# DRO.net
KiCad netlist of a schematic drawn in EAGLE
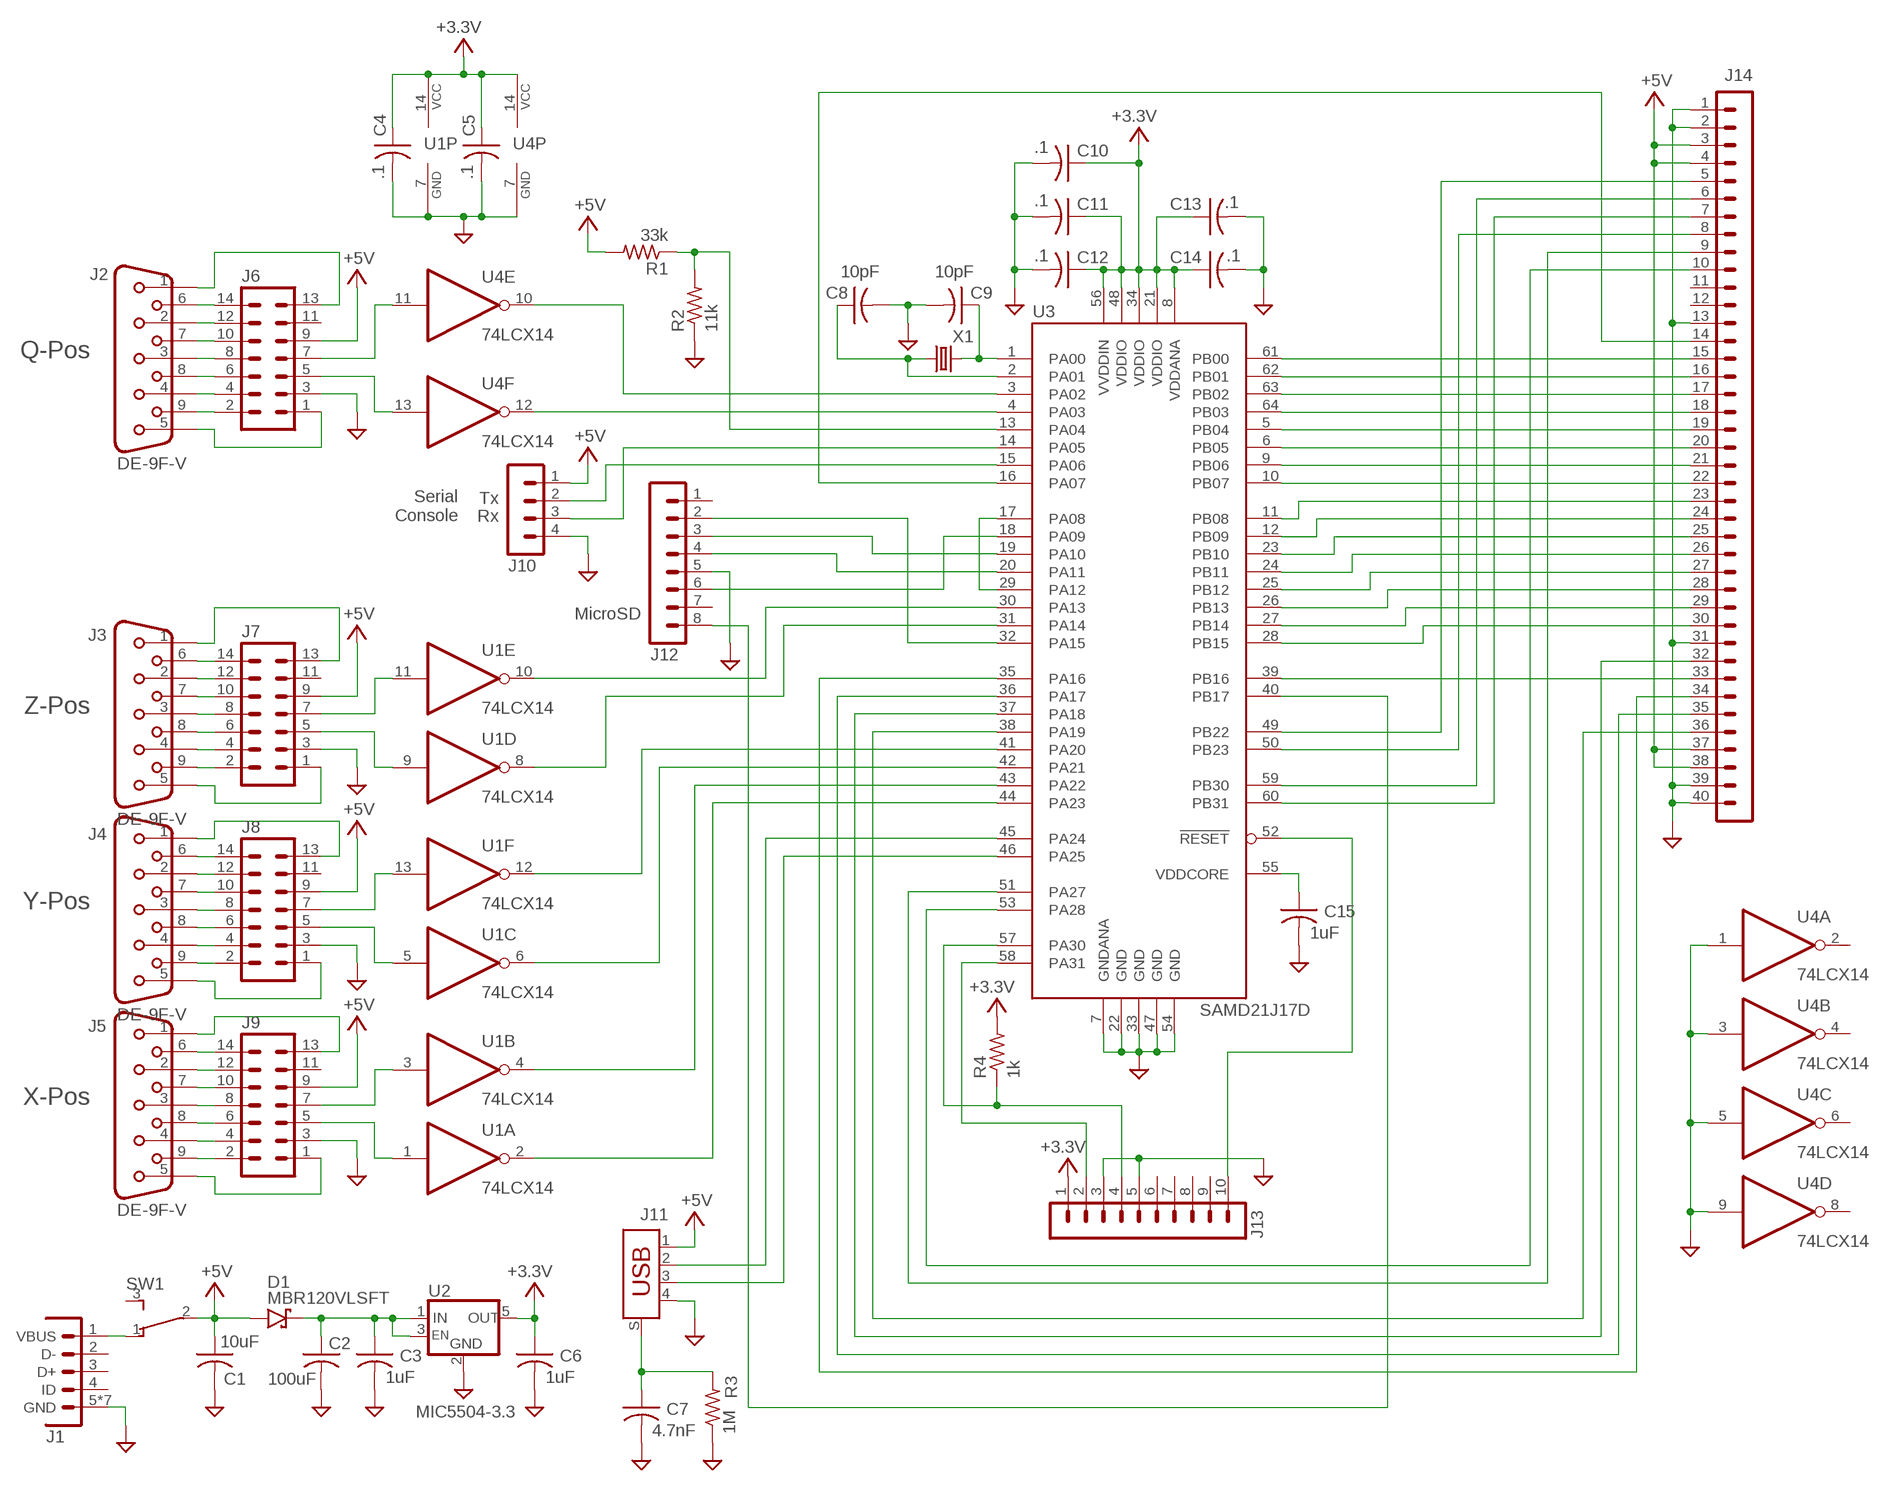
[diagram p0: schematic, sheet 1]

(export (version "E")
  (design (tool "Eeschema 10.0.6"))
  (components
    (comp (ref "C1")
      (value "10uF")
      (footprint "eagle-import:0603")
      (libsource (lib "eagle-import") (part "C-US0603"))
    )
    (comp (ref "C2")
      (value "100uF")
      (footprint "eagle-import:C1206")
      (libsource (lib "eagle-import") (part "C-USC1206"))
    )
    (comp (ref "C3")
      (value "1uF")
      (footprint "eagle-import:0603")
      (libsource (lib "eagle-import") (part "C-US0603"))
    )
    (comp (ref "C4")
      (value ".1")
      (footprint "eagle-import:0603")
      (libsource (lib "eagle-import") (part "C-US0603"))
    )
    (comp (ref "C5")
      (value ".1")
      (footprint "eagle-import:0603")
      (libsource (lib "eagle-import") (part "C-US0603"))
    )
    (comp (ref "C6")
      (value "1uF")
      (footprint "eagle-import:0603")
      (libsource (lib "eagle-import") (part "C-US0603"))
    )
    (comp (ref "C7")
      (value "4.7nF")
      (footprint "eagle-import:0603")
      (libsource (lib "eagle-import") (part "C-US0603"))
    )
    (comp (ref "C8")
      (value "10pF")
      (footprint "eagle-import:0603")
      (libsource (lib "eagle-import") (part "C-US0603"))
    )
    (comp (ref "C9")
      (value "10pF")
      (footprint "eagle-import:0603")
      (libsource (lib "eagle-import") (part "C-US0603"))
    )
    (comp (ref "C10")
      (value ".1")
      (footprint "eagle-import:0603")
      (libsource (lib "eagle-import") (part "C-US0603"))
    )
    (comp (ref "C11")
      (value ".1")
      (footprint "eagle-import:0603")
      (libsource (lib "eagle-import") (part "C-US0603"))
    )
    (comp (ref "C12")
      (value ".1")
      (footprint "eagle-import:0603")
      (libsource (lib "eagle-import") (part "C-US0603"))
    )
    (comp (ref "C13")
      (value ".1")
      (footprint "eagle-import:0603")
      (libsource (lib "eagle-import") (part "C-US0603"))
    )
    (comp (ref "C14")
      (value ".1")
      (footprint "eagle-import:0603")
      (libsource (lib "eagle-import") (part "C-US0603"))
    )
    (comp (ref "C15")
      (value "1uF")
      (footprint "eagle-import:0603")
      (libsource (lib "eagle-import") (part "C-US0603"))
    )
    (comp (ref "D1")
      (value "MBR120VLSFT")
      (footprint "eagle-import:SOD123")
      (libsource (lib "eagle-import") (part "SCHOTTKY-DIODE-SOD-123"))
    )
    (comp (ref "J1")
      (value "USB_MINI-B-MICRO-B_FCI")
      (footprint "eagle-import:USB_MICRO-B_FCI")
      (libsource (lib "eagle-import") (part "USB_MINI-B-MICRO-B_FCI"))
    )
    (comp (ref "J2")
      (value "DE-9F-V")
      (footprint "eagle-import:DE-9F-PCB-VERT")
      (libsource (lib "eagle-import") (part "DE-9F-V"))
    )
    (comp (ref "J3")
      (value "DE-9F-V")
      (footprint "eagle-import:DE-9F-PCB-VERT")
      (libsource (lib "eagle-import") (part "DE-9F-V"))
    )
    (comp (ref "J4")
      (value "DE-9F-V")
      (footprint "eagle-import:DE-9F-PCB-VERT")
      (libsource (lib "eagle-import") (part "DE-9F-V"))
    )
    (comp (ref "J5")
      (value "DE-9F-V")
      (footprint "eagle-import:DE-9F-PCB-VERT")
      (libsource (lib "eagle-import") (part "DE-9F-V"))
    )
    (comp (ref "J6")
      (value "CONN-14-BIDI")
      (footprint "eagle-import:CONN-1.27X2-14")
      (libsource (lib "eagle-import") (part "CONN-14-BIDI"))
    )
    (comp (ref "J7")
      (value "CONN-14-BIDI")
      (footprint "eagle-import:CONN-1.27X2-14")
      (libsource (lib "eagle-import") (part "CONN-14-BIDI"))
    )
    (comp (ref "J8")
      (value "CONN-14-BIDI")
      (footprint "eagle-import:CONN-1.27X2-14")
      (libsource (lib "eagle-import") (part "CONN-14-BIDI"))
    )
    (comp (ref "J9")
      (value "CONN-14-BIDI")
      (footprint "eagle-import:CONN-1.27X2-14")
      (libsource (lib "eagle-import") (part "CONN-14-BIDI"))
    )
    (comp (ref "J10")
      (value "CONN-4-2.54X1-RA")
      (footprint "eagle-import:CONN-2.54X1-4-RA")
      (libsource (lib "eagle-import") (part "CONN-4-2.54X1-RA"))
    )
    (comp (ref "J11")
      (value "USB-A-SHIELD")
      (footprint "eagle-import:USB-A")
      (libsource (lib "eagle-import") (part "USB-A-SHIELD"))
    )
    (comp (ref "J12")
      (value "CONN-8-2.54X2")
      (footprint "eagle-import:CONN-2.54X2-8")
      (libsource (lib "eagle-import") (part "CONN-8-2.54X2"))
    )
    (comp (ref "J13")
      (value "CONN-10-ARM")
      (footprint "eagle-import:CONN-1.27X2-10")
      (libsource (lib "eagle-import") (part "CONN-10-ARM"))
    )
    (comp (ref "J14")
      (value "CONN-40")
      (footprint "eagle-import:CONN-2.54X2-40")
      (libsource (lib "eagle-import") (part "CONN-40"))
    )
    (comp (ref "R1")
      (value "33k")
      (footprint "eagle-import:0603")
      (libsource (lib "eagle-import") (part "R-US0603"))
    )
    (comp (ref "R2")
      (value "11k")
      (footprint "eagle-import:0603")
      (libsource (lib "eagle-import") (part "R-US0603"))
    )
    (comp (ref "R3")
      (value "1M")
      (footprint "eagle-import:0603")
      (libsource (lib "eagle-import") (part "R-US0603"))
    )
    (comp (ref "R4")
      (value "1k")
      (footprint "eagle-import:0603")
      (libsource (lib "eagle-import") (part "R-US0603"))
    )
    (comp (ref "SW1")
      (value "SWITCH-SPDT-MINI-RA-SHORT")
      (footprint "eagle-import:SWITCH-SPDT-MINI-RA-SHORT")
      (libsource (lib "eagle-import") (part "SWITCH-SPDT-MINI-RA-SHORT"))
    )
    (comp (ref "U1")
      (value "74LCX14")
      (footprint "eagle-import:TSSOP14")
      (libsource (lib "eagle-import") (part "7404M"))
    )
    (comp (ref "U2")
      (value "MIC5504-3.3")
      (footprint "eagle-import:SOT23-5")
      (libsource (lib "eagle-import") (part "VREG-ENABLE"))
    )
    (comp (ref "U3")
      (value "SAMD21J17D")
      (footprint "eagle-import:TQFP64-0.5")
      (libsource (lib "eagle-import") (part "ATSAMD21JA"))
    )
    (comp (ref "U4")
      (value "74LCX14")
      (footprint "eagle-import:TSSOP14")
      (libsource (lib "eagle-import") (part "7404M"))
    )
    (comp (ref "X1")
      (value "CRYSTAL-3X1.5")
      (footprint "eagle-import:XTAL-SMD-3.2X1.5-2PIN")
      (libsource (lib "eagle-import") (part "CRYSTAL-3X1.5"))
    )
  )
  (nets
    (net (code "1") (name "+3.3V") (class "Default")
      (node (ref "C10") (pin "1") (pinfunction "1_1") (pintype "passive"))
      (node (ref "C11") (pin "1") (pinfunction "1_1") (pintype "passive"))
      (node (ref "C12") (pin "1") (pinfunction "1_1") (pintype "passive"))
      (node (ref "C13") (pin "1") (pinfunction "1_1") (pintype "passive"))
      (node (ref "C14") (pin "1") (pinfunction "1_1") (pintype "passive"))
      (node (ref "C4") (pin "1") (pinfunction "1_1") (pintype "passive"))
      (node (ref "C5") (pin "1") (pinfunction "1_1") (pintype "passive"))
      (node (ref "C6") (pin "1") (pinfunction "1_1") (pintype "passive"))
      (node (ref "J13") (pin "1") (pinfunction "1_1") (pintype "passive"))
      (node (ref "R4") (pin "2") (pinfunction "2_2") (pintype "passive"))
      (node (ref "U1") (pin "14") (pinfunction "VCC_14") (pintype "power_in"))
      (node (ref "U2") (pin "5") (pinfunction "OUT_5") (pintype "passive"))
      (node (ref "U3") (pin "21") (pinfunction "VDDIO_21") (pintype "power_in"))
      (node (ref "U3") (pin "34") (pinfunction "VDDIO_34") (pintype "power_in"))
      (node (ref "U3") (pin "48") (pinfunction "VDDIO_48") (pintype "power_in"))
      (node (ref "U3") (pin "56") (pinfunction "VVDDIN_56") (pintype "power_in"))
      (node (ref "U3") (pin "8") (pinfunction "VDDANA_8") (pintype "power_in"))
      (node (ref "U4") (pin "14") (pinfunction "VCC_14") (pintype "power_in"))
    )
    (net (code "2") (name "+5V") (class "Default")
      (node (ref "C1") (pin "1") (pinfunction "1_1") (pintype "passive"))
      (node (ref "D1") (pin "A") (pinfunction "A_A") (pintype "passive"))
      (node (ref "J10") (pin "1") (pinfunction "1_1") (pintype "passive"))
      (node (ref "J11") (pin "1") (pinfunction "1_1") (pintype "passive"))
      (node (ref "J14") (pin "3") (pinfunction "P3_3") (pintype "passive"))
      (node (ref "J14") (pin "37") (pinfunction "P37_37") (pintype "passive"))
      (node (ref "J14") (pin "38") (pinfunction "P38_38") (pintype "passive"))
      (node (ref "J14") (pin "4") (pinfunction "P4_4") (pintype "passive"))
      (node (ref "J6") (pin "9") (pinfunction "9_9") (pintype "passive"))
      (node (ref "J7") (pin "9") (pinfunction "9_9") (pintype "passive"))
      (node (ref "J8") (pin "9") (pinfunction "9_9") (pintype "passive"))
      (node (ref "J9") (pin "9") (pinfunction "9_9") (pintype "passive"))
      (node (ref "R1") (pin "2") (pinfunction "2_2") (pintype "passive"))
      (node (ref "SW1") (pin "2") (pinfunction "C_2") (pintype "passive"))
    )
    (net (code "3") (name "GND") (class "Default")
      (node (ref "C1") (pin "2") (pinfunction "2_2") (pintype "passive"))
      (node (ref "C10") (pin "2") (pinfunction "2_2") (pintype "passive"))
      (node (ref "C11") (pin "2") (pinfunction "2_2") (pintype "passive"))
      (node (ref "C12") (pin "2") (pinfunction "2_2") (pintype "passive"))
      (node (ref "C13") (pin "2") (pinfunction "2_2") (pintype "passive"))
      (node (ref "C14") (pin "2") (pinfunction "2_2") (pintype "passive"))
      (node (ref "C15") (pin "2") (pinfunction "2_2") (pintype "passive"))
      (node (ref "C2") (pin "2") (pinfunction "2_2") (pintype "passive"))
      (node (ref "C3") (pin "2") (pinfunction "2_2") (pintype "passive"))
      (node (ref "C4") (pin "2") (pinfunction "2_2") (pintype "passive"))
      (node (ref "C5") (pin "2") (pinfunction "2_2") (pintype "passive"))
      (node (ref "C6") (pin "2") (pinfunction "2_2") (pintype "passive"))
      (node (ref "C7") (pin "2") (pinfunction "2_2") (pintype "passive"))
      (node (ref "C8") (pin "2") (pinfunction "2_2") (pintype "passive"))
      (node (ref "C9") (pin "2") (pinfunction "2_2") (pintype "passive"))
      (node (ref "J1") (pin "5") (pinfunction "GND_5") (pintype "power_in"))
      (node (ref "J1") (pin "SHELL1") (pinfunction "GND_SHELL1") (pintype "power_in"))
      (node (ref "J1") (pin "SHELL2") (pinfunction "GND_SHELL2") (pintype "power_in"))
      (node (ref "J1") (pin "SHELL3") (pinfunction "GND_SHELL3") (pintype "power_in"))
      (node (ref "J1") (pin "SHELL4") (pinfunction "GND_SHELL4") (pintype "power_in"))
      (node (ref "J1") (pin "SHELL5") (pinfunction "GND_SHELL5") (pintype "power_in"))
      (node (ref "J1") (pin "SHELL6") (pinfunction "GND_SHELL6") (pintype "power_in"))
      (node (ref "J10") (pin "4") (pinfunction "4_4") (pintype "passive"))
      (node (ref "J11") (pin "4") (pinfunction "4_4") (pintype "passive"))
      (node (ref "J12") (pin "5") (pinfunction "5_5") (pintype "passive"))
      (node (ref "J13") (pin "3") (pinfunction "3_3") (pintype "passive"))
      (node (ref "J13") (pin "5") (pinfunction "5_5") (pintype "passive"))
      (node (ref "J14") (pin "1") (pinfunction "P1_1") (pintype "passive"))
      (node (ref "J14") (pin "13") (pinfunction "P13_13") (pintype "passive"))
      (node (ref "J14") (pin "2") (pinfunction "P2_2") (pintype "passive"))
      (node (ref "J14") (pin "31") (pinfunction "P31_31") (pintype "passive"))
      (node (ref "J14") (pin "39") (pinfunction "P39_39") (pintype "passive"))
      (node (ref "J14") (pin "40") (pinfunction "P40_40") (pintype "passive"))
      (node (ref "J6") (pin "3") (pinfunction "3_3") (pintype "passive"))
      (node (ref "J7") (pin "3") (pinfunction "3_3") (pintype "passive"))
      (node (ref "J8") (pin "3") (pinfunction "3_3") (pintype "passive"))
      (node (ref "J9") (pin "3") (pinfunction "3_3") (pintype "passive"))
      (node (ref "R2") (pin "1") (pinfunction "1_1") (pintype "passive"))
      (node (ref "R3") (pin "1") (pinfunction "1_1") (pintype "passive"))
      (node (ref "U1") (pin "7") (pinfunction "GND_7") (pintype "power_in"))
      (node (ref "U2") (pin "2") (pinfunction "GND_2") (pintype "power_in"))
      (node (ref "U3") (pin "22") (pinfunction "GND_22") (pintype "power_in"))
      (node (ref "U3") (pin "33") (pinfunction "GND_33") (pintype "power_in"))
      (node (ref "U3") (pin "47") (pinfunction "GND_47") (pintype "power_in"))
      (node (ref "U3") (pin "54") (pinfunction "GND_54") (pintype "power_in"))
      (node (ref "U3") (pin "7") (pinfunction "GNDANA_7") (pintype "power_in"))
      (node (ref "U4") (pin "1") (pinfunction "I_1") (pintype "input"))
      (node (ref "U4") (pin "3") (pinfunction "I_3") (pintype "input"))
      (node (ref "U4") (pin "5") (pinfunction "I_5") (pintype "input"))
      (node (ref "U4") (pin "7") (pinfunction "GND_7") (pintype "power_in"))
      (node (ref "U4") (pin "9") (pinfunction "I_9") (pintype "input"))
    )
    (net (code "4") (name "Net-(J1-VBUS)") (class "Default")
      (node (ref "J1") (pin "1") (pinfunction "VBUS_1") (pintype "power_in"))
      (node (ref "SW1") (pin "1") (pinfunction "NC_1") (pintype "passive"))
    )
    (net (code "5") (name "Net-(J2-Pad1)") (class "Default")
      (node (ref "J2") (pin "1") (pinfunction "1_1") (pintype "passive"))
      (node (ref "J6") (pin "13") (pinfunction "13_13") (pintype "passive"))
    )
    (net (code "6") (name "Net-(J2-Pad2)") (class "Default")
      (node (ref "J2") (pin "2") (pinfunction "2_2") (pintype "passive"))
      (node (ref "J6") (pin "12") (pinfunction "12_12") (pintype "passive"))
    )
    (net (code "7") (name "Net-(J2-Pad3)") (class "Default")
      (node (ref "J2") (pin "3") (pinfunction "3_3") (pintype "passive"))
      (node (ref "J6") (pin "8") (pinfunction "8_8") (pintype "passive"))
    )
    (net (code "8") (name "Net-(J2-Pad4)") (class "Default")
      (node (ref "J2") (pin "4") (pinfunction "4_4") (pintype "passive"))
      (node (ref "J6") (pin "4") (pinfunction "4_4") (pintype "passive"))
    )
    (net (code "9") (name "Net-(J2-Pad5)") (class "Default")
      (node (ref "J2") (pin "5") (pinfunction "5_5") (pintype "passive"))
      (node (ref "J6") (pin "1") (pinfunction "1_1") (pintype "passive"))
    )
    (net (code "10") (name "Net-(J2-Pad6)") (class "Default")
      (node (ref "J2") (pin "6") (pinfunction "6_6") (pintype "passive"))
      (node (ref "J6") (pin "14") (pinfunction "14_14") (pintype "passive"))
    )
    (net (code "11") (name "Net-(J2-Pad7)") (class "Default")
      (node (ref "J2") (pin "7") (pinfunction "7_7") (pintype "passive"))
      (node (ref "J6") (pin "10") (pinfunction "10_10") (pintype "passive"))
    )
    (net (code "12") (name "Net-(J2-Pad8)") (class "Default")
      (node (ref "J2") (pin "8") (pinfunction "8_8") (pintype "passive"))
      (node (ref "J6") (pin "6") (pinfunction "6_6") (pintype "passive"))
    )
    (net (code "13") (name "Net-(J2-Pad9)") (class "Default")
      (node (ref "J2") (pin "9") (pinfunction "9_9") (pintype "passive"))
      (node (ref "J6") (pin "2") (pinfunction "2_2") (pintype "passive"))
    )
    (net (code "14") (name "Net-(J3-Pad1)") (class "Default")
      (node (ref "J3") (pin "1") (pinfunction "1_1") (pintype "passive"))
      (node (ref "J7") (pin "13") (pinfunction "13_13") (pintype "passive"))
    )
    (net (code "15") (name "Net-(J3-Pad2)") (class "Default")
      (node (ref "J3") (pin "2") (pinfunction "2_2") (pintype "passive"))
      (node (ref "J7") (pin "12") (pinfunction "12_12") (pintype "passive"))
    )
    (net (code "16") (name "Net-(J3-Pad3)") (class "Default")
      (node (ref "J3") (pin "3") (pinfunction "3_3") (pintype "passive"))
      (node (ref "J7") (pin "8") (pinfunction "8_8") (pintype "passive"))
    )
    (net (code "17") (name "Net-(J3-Pad4)") (class "Default")
      (node (ref "J3") (pin "4") (pinfunction "4_4") (pintype "passive"))
      (node (ref "J7") (pin "4") (pinfunction "4_4") (pintype "passive"))
    )
    (net (code "18") (name "Net-(J3-Pad5)") (class "Default")
      (node (ref "J3") (pin "5") (pinfunction "5_5") (pintype "passive"))
      (node (ref "J7") (pin "1") (pinfunction "1_1") (pintype "passive"))
    )
    (net (code "19") (name "Net-(J3-Pad6)") (class "Default")
      (node (ref "J3") (pin "6") (pinfunction "6_6") (pintype "passive"))
      (node (ref "J7") (pin "14") (pinfunction "14_14") (pintype "passive"))
    )
    (net (code "20") (name "Net-(J3-Pad7)") (class "Default")
      (node (ref "J3") (pin "7") (pinfunction "7_7") (pintype "passive"))
      (node (ref "J7") (pin "10") (pinfunction "10_10") (pintype "passive"))
    )
    (net (code "21") (name "Net-(J3-Pad8)") (class "Default")
      (node (ref "J3") (pin "8") (pinfunction "8_8") (pintype "passive"))
      (node (ref "J7") (pin "6") (pinfunction "6_6") (pintype "passive"))
    )
    (net (code "22") (name "Net-(J3-Pad9)") (class "Default")
      (node (ref "J3") (pin "9") (pinfunction "9_9") (pintype "passive"))
      (node (ref "J7") (pin "2") (pinfunction "2_2") (pintype "passive"))
    )
    (net (code "23") (name "Net-(J4-Pad1)") (class "Default")
      (node (ref "J4") (pin "1") (pinfunction "1_1") (pintype "passive"))
      (node (ref "J8") (pin "13") (pinfunction "13_13") (pintype "passive"))
    )
    (net (code "24") (name "Net-(J4-Pad2)") (class "Default")
      (node (ref "J4") (pin "2") (pinfunction "2_2") (pintype "passive"))
      (node (ref "J8") (pin "12") (pinfunction "12_12") (pintype "passive"))
    )
    (net (code "25") (name "Net-(J4-Pad3)") (class "Default")
      (node (ref "J4") (pin "3") (pinfunction "3_3") (pintype "passive"))
      (node (ref "J8") (pin "8") (pinfunction "8_8") (pintype "passive"))
    )
    (net (code "26") (name "Net-(J4-Pad4)") (class "Default")
      (node (ref "J4") (pin "4") (pinfunction "4_4") (pintype "passive"))
      (node (ref "J8") (pin "4") (pinfunction "4_4") (pintype "passive"))
    )
    (net (code "27") (name "Net-(J4-Pad5)") (class "Default")
      (node (ref "J4") (pin "5") (pinfunction "5_5") (pintype "passive"))
      (node (ref "J8") (pin "1") (pinfunction "1_1") (pintype "passive"))
    )
    (net (code "28") (name "Net-(J4-Pad6)") (class "Default")
      (node (ref "J4") (pin "6") (pinfunction "6_6") (pintype "passive"))
      (node (ref "J8") (pin "14") (pinfunction "14_14") (pintype "passive"))
    )
    (net (code "29") (name "Net-(J4-Pad7)") (class "Default")
      (node (ref "J4") (pin "7") (pinfunction "7_7") (pintype "passive"))
      (node (ref "J8") (pin "10") (pinfunction "10_10") (pintype "passive"))
    )
    (net (code "30") (name "Net-(J4-Pad8)") (class "Default")
      (node (ref "J4") (pin "8") (pinfunction "8_8") (pintype "passive"))
      (node (ref "J8") (pin "6") (pinfunction "6_6") (pintype "passive"))
    )
    (net (code "31") (name "Net-(J4-Pad9)") (class "Default")
      (node (ref "J4") (pin "9") (pinfunction "9_9") (pintype "passive"))
      (node (ref "J8") (pin "2") (pinfunction "2_2") (pintype "passive"))
    )
    (net (code "32") (name "Net-(J5-Pad1)") (class "Default")
      (node (ref "J5") (pin "1") (pinfunction "1_1") (pintype "passive"))
      (node (ref "J9") (pin "13") (pinfunction "13_13") (pintype "passive"))
    )
    (net (code "33") (name "Net-(J5-Pad2)") (class "Default")
      (node (ref "J5") (pin "2") (pinfunction "2_2") (pintype "passive"))
      (node (ref "J9") (pin "12") (pinfunction "12_12") (pintype "passive"))
    )
    (net (code "34") (name "Net-(J5-Pad3)") (class "Default")
      (node (ref "J5") (pin "3") (pinfunction "3_3") (pintype "passive"))
      (node (ref "J9") (pin "8") (pinfunction "8_8") (pintype "passive"))
    )
    (net (code "35") (name "Net-(J5-Pad4)") (class "Default")
      (node (ref "J5") (pin "4") (pinfunction "4_4") (pintype "passive"))
      (node (ref "J9") (pin "4") (pinfunction "4_4") (pintype "passive"))
    )
    (net (code "36") (name "Net-(J5-Pad5)") (class "Default")
      (node (ref "J5") (pin "5") (pinfunction "5_5") (pintype "passive"))
      (node (ref "J9") (pin "1") (pinfunction "1_1") (pintype "passive"))
    )
    (net (code "37") (name "Net-(J5-Pad6)") (class "Default")
      (node (ref "J5") (pin "6") (pinfunction "6_6") (pintype "passive"))
      (node (ref "J9") (pin "14") (pinfunction "14_14") (pintype "passive"))
    )
    (net (code "38") (name "Net-(J5-Pad7)") (class "Default")
      (node (ref "J5") (pin "7") (pinfunction "7_7") (pintype "passive"))
      (node (ref "J9") (pin "10") (pinfunction "10_10") (pintype "passive"))
    )
    (net (code "39") (name "Net-(J5-Pad8)") (class "Default")
      (node (ref "J5") (pin "8") (pinfunction "8_8") (pintype "passive"))
      (node (ref "J9") (pin "6") (pinfunction "6_6") (pintype "passive"))
    )
    (net (code "40") (name "Net-(J5-Pad9)") (class "Default")
      (node (ref "J5") (pin "9") (pinfunction "9_9") (pintype "passive"))
      (node (ref "J9") (pin "2") (pinfunction "2_2") (pintype "passive"))
    )
    (net (code "41") (name "Net-(J11-SHIELD)") (class "Default")
      (node (ref "C7") (pin "1") (pinfunction "1_1") (pintype "passive"))
      (node (ref "J11") (pin "S") (pinfunction "SHIELD_S") (pintype "passive"))
      (node (ref "R3") (pin "2") (pinfunction "2_2") (pintype "passive"))
    )
    (net (code "42") (name "Net-(J14-P5)") (class "Default")
      (node (ref "J14") (pin "5") (pinfunction "P5_5") (pintype "passive"))
      (node (ref "U3") (pin "49") (pinfunction "PB22_49") (pintype "bidirectional"))
    )
    (net (code "43") (name "Net-(J14-P6)") (class "Default")
      (node (ref "J14") (pin "6") (pinfunction "P6_6") (pintype "passive"))
      (node (ref "U3") (pin "59") (pinfunction "PB30_59") (pintype "bidirectional"))
    )
    (net (code "44") (name "Net-(J14-P7)") (class "Default")
      (node (ref "J14") (pin "7") (pinfunction "P7_7") (pintype "passive"))
      (node (ref "U3") (pin "60") (pinfunction "PB31_60") (pintype "bidirectional"))
    )
    (net (code "45") (name "Net-(J14-P8)") (class "Default")
      (node (ref "J14") (pin "8") (pinfunction "P8_8") (pintype "passive"))
      (node (ref "U3") (pin "50") (pinfunction "PB23_50") (pintype "bidirectional"))
    )
    (net (code "46") (name "Net-(J14-P9)") (class "Default")
      (node (ref "J14") (pin "9") (pinfunction "P9_9") (pintype "passive"))
      (node (ref "U3") (pin "51") (pinfunction "PA27_51") (pintype "bidirectional"))
    )
    (net (code "47") (name "Net-(J14-P10)") (class "Default")
      (node (ref "J14") (pin "10") (pinfunction "P10_10") (pintype "passive"))
      (node (ref "U3") (pin "53") (pinfunction "PA28_53") (pintype "bidirectional"))
    )
    (net (code "48") (name "Net-(J14-P14)") (class "Default")
      (node (ref "J14") (pin "14") (pinfunction "P14_14") (pintype "passive"))
      (node (ref "U3") (pin "16") (pinfunction "PA07_16") (pintype "bidirectional"))
    )
    (net (code "49") (name "Net-(J14-P15)") (class "Default")
      (node (ref "J14") (pin "15") (pinfunction "P15_15") (pintype "passive"))
      (node (ref "U3") (pin "61") (pinfunction "PB00_61") (pintype "bidirectional"))
    )
    (net (code "50") (name "Net-(J14-P16)") (class "Default")
      (node (ref "J14") (pin "16") (pinfunction "P16_16") (pintype "passive"))
      (node (ref "U3") (pin "62") (pinfunction "PB01_62") (pintype "bidirectional"))
    )
    (net (code "51") (name "Net-(J14-P17)") (class "Default")
      (node (ref "J14") (pin "17") (pinfunction "P17_17") (pintype "passive"))
      (node (ref "U3") (pin "63") (pinfunction "PB02_63") (pintype "bidirectional"))
    )
    (net (code "52") (name "Net-(J14-P18)") (class "Default")
      (node (ref "J14") (pin "18") (pinfunction "P18_18") (pintype "passive"))
      (node (ref "U3") (pin "64") (pinfunction "PB03_64") (pintype "bidirectional"))
    )
    (net (code "53") (name "Net-(J14-P19)") (class "Default")
      (node (ref "J14") (pin "19") (pinfunction "P19_19") (pintype "passive"))
      (node (ref "U3") (pin "5") (pinfunction "PB04_5") (pintype "bidirectional"))
    )
    (net (code "54") (name "Net-(J14-P20)") (class "Default")
      (node (ref "J14") (pin "20") (pinfunction "P20_20") (pintype "passive"))
      (node (ref "U3") (pin "6") (pinfunction "PB05_6") (pintype "bidirectional"))
    )
    (net (code "55") (name "Net-(J14-P21)") (class "Default")
      (node (ref "J14") (pin "21") (pinfunction "P21_21") (pintype "passive"))
      (node (ref "U3") (pin "9") (pinfunction "PB06_9") (pintype "bidirectional"))
    )
    (net (code "56") (name "Net-(J14-P22)") (class "Default")
      (node (ref "J14") (pin "22") (pinfunction "P22_22") (pintype "passive"))
      (node (ref "U3") (pin "10") (pinfunction "PB07_10") (pintype "bidirectional"))
    )
    (net (code "57") (name "Net-(J14-P23)") (class "Default")
      (node (ref "J14") (pin "23") (pinfunction "P23_23") (pintype "passive"))
      (node (ref "U3") (pin "11") (pinfunction "PB08_11") (pintype "bidirectional"))
    )
    (net (code "58") (name "Net-(J14-P24)") (class "Default")
      (node (ref "J14") (pin "24") (pinfunction "P24_24") (pintype "passive"))
      (node (ref "U3") (pin "12") (pinfunction "PB09_12") (pintype "bidirectional"))
    )
    (net (code "59") (name "Net-(J14-P25)") (class "Default")
      (node (ref "J14") (pin "25") (pinfunction "P25_25") (pintype "passive"))
      (node (ref "U3") (pin "23") (pinfunction "PB10_23") (pintype "bidirectional"))
    )
    (net (code "60") (name "Net-(J14-P26)") (class "Default")
      (node (ref "J14") (pin "26") (pinfunction "P26_26") (pintype "passive"))
      (node (ref "U3") (pin "24") (pinfunction "PB11_24") (pintype "bidirectional"))
    )
    (net (code "61") (name "Net-(J14-P27)") (class "Default")
      (node (ref "J14") (pin "27") (pinfunction "P27_27") (pintype "passive"))
      (node (ref "U3") (pin "25") (pinfunction "PB12_25") (pintype "bidirectional"))
    )
    (net (code "62") (name "Net-(J14-P28)") (class "Default")
      (node (ref "J14") (pin "28") (pinfunction "P28_28") (pintype "passive"))
      (node (ref "U3") (pin "26") (pinfunction "PB13_26") (pintype "bidirectional"))
    )
    (net (code "63") (name "Net-(J14-P29)") (class "Default")
      (node (ref "J14") (pin "29") (pinfunction "P29_29") (pintype "passive"))
      (node (ref "U3") (pin "27") (pinfunction "PB14_27") (pintype "bidirectional"))
    )
    (net (code "64") (name "Net-(J14-P30)") (class "Default")
      (node (ref "J14") (pin "30") (pinfunction "P30_30") (pintype "passive"))
      (node (ref "U3") (pin "28") (pinfunction "PB15_28") (pintype "bidirectional"))
    )
    (net (code "65") (name "Net-(J14-P32)") (class "Default")
      (node (ref "J14") (pin "32") (pinfunction "P32_32") (pintype "passive"))
      (node (ref "U3") (pin "37") (pinfunction "PA18_37") (pintype "bidirectional"))
    )
    (net (code "66") (name "Net-(J14-P33)") (class "Default")
      (node (ref "J14") (pin "33") (pinfunction "P33_33") (pintype "passive"))
      (node (ref "U3") (pin "39") (pinfunction "PB16_39") (pintype "bidirectional"))
    )
    (net (code "67") (name "Net-(J14-P34)") (class "Default")
      (node (ref "J14") (pin "34") (pinfunction "P34_34") (pintype "passive"))
      (node (ref "U3") (pin "35") (pinfunction "PA16_35") (pintype "bidirectional"))
    )
    (net (code "68") (name "Net-(J14-P35)") (class "Default")
      (node (ref "J14") (pin "35") (pinfunction "P35_35") (pintype "passive"))
      (node (ref "U3") (pin "36") (pinfunction "PA17_36") (pintype "bidirectional"))
    )
    (net (code "69") (name "Net-(J14-P36)") (class "Default")
      (node (ref "J14") (pin "36") (pinfunction "P36_36") (pintype "passive"))
      (node (ref "U3") (pin "38") (pinfunction "PA19_38") (pintype "bidirectional"))
    )
    (net (code "70") (name "Net-(U1A-I)") (class "Default")
      (node (ref "J9") (pin "5") (pinfunction "5_5") (pintype "passive"))
      (node (ref "U1") (pin "1") (pinfunction "I_1") (pintype "input"))
    )
    (net (code "71") (name "Net-(U1A-O)") (class "Default")
      (node (ref "U1") (pin "2") (pinfunction "O_2") (pintype "output"))
      (node (ref "U3") (pin "44") (pinfunction "PA23_44") (pintype "bidirectional"))
    )
    (net (code "72") (name "Net-(U1B-I)") (class "Default")
      (node (ref "J9") (pin "7") (pinfunction "7_7") (pintype "passive"))
      (node (ref "U1") (pin "3") (pinfunction "I_3") (pintype "input"))
    )
    (net (code "73") (name "Net-(U1B-O)") (class "Default")
      (node (ref "U1") (pin "4") (pinfunction "O_4") (pintype "output"))
      (node (ref "U3") (pin "43") (pinfunction "PA22_43") (pintype "bidirectional"))
    )
    (net (code "74") (name "Net-(U1C-I)") (class "Default")
      (node (ref "J8") (pin "5") (pinfunction "5_5") (pintype "passive"))
      (node (ref "U1") (pin "5") (pinfunction "I_5") (pintype "input"))
    )
    (net (code "75") (name "Net-(U1C-O)") (class "Default")
      (node (ref "U1") (pin "6") (pinfunction "O_6") (pintype "output"))
      (node (ref "U3") (pin "42") (pinfunction "PA21_42") (pintype "bidirectional"))
    )
    (net (code "76") (name "Net-(U1D-I)") (class "Default")
      (node (ref "J7") (pin "5") (pinfunction "5_5") (pintype "passive"))
      (node (ref "U1") (pin "9") (pinfunction "I_9") (pintype "input"))
    )
    (net (code "77") (name "Net-(U1D-O)") (class "Default")
      (node (ref "U1") (pin "8") (pinfunction "O_8") (pintype "output"))
      (node (ref "U3") (pin "31") (pinfunction "PA14_31") (pintype "bidirectional"))
    )
    (net (code "78") (name "Net-(U1E-I)") (class "Default")
      (node (ref "J7") (pin "7") (pinfunction "7_7") (pintype "passive"))
      (node (ref "U1") (pin "11") (pinfunction "I_11") (pintype "input"))
    )
    (net (code "79") (name "Net-(U1E-O)") (class "Default")
      (node (ref "U1") (pin "10") (pinfunction "O_10") (pintype "output"))
      (node (ref "U3") (pin "30") (pinfunction "PA13_30") (pintype "bidirectional"))
    )
    (net (code "80") (name "Net-(U1F-I)") (class "Default")
      (node (ref "J8") (pin "7") (pinfunction "7_7") (pintype "passive"))
      (node (ref "U1") (pin "13") (pinfunction "I_13") (pintype "input"))
    )
    (net (code "81") (name "Net-(U1F-O)") (class "Default")
      (node (ref "U1") (pin "12") (pinfunction "O_12") (pintype "output"))
      (node (ref "U3") (pin "41") (pinfunction "PA20_41") (pintype "bidirectional"))
    )
    (net (code "82") (name "Net-(U2-EN)") (class "Default")
      (node (ref "C2") (pin "1") (pinfunction "1_1") (pintype "passive"))
      (node (ref "C3") (pin "1") (pinfunction "1_1") (pintype "passive"))
      (node (ref "D1") (pin "C") (pinfunction "C_C") (pintype "passive"))
      (node (ref "U2") (pin "1") (pinfunction "IN_1") (pintype "input"))
      (node (ref "U2") (pin "3") (pinfunction "EN_3") (pintype "input"))
    )
    (net (code "83") (name "Net-(U3-PA00)") (class "Default")
      (node (ref "C9") (pin "1") (pinfunction "1_1") (pintype "passive"))
      (node (ref "U3") (pin "1") (pinfunction "PA00_1") (pintype "bidirectional"))
      (node (ref "X1") (pin "2") (pinfunction "2_2") (pintype "passive"))
    )
    (net (code "84") (name "Net-(U3-PA01)") (class "Default")
      (node (ref "C8") (pin "1") (pinfunction "1_1") (pintype "passive"))
      (node (ref "U3") (pin "2") (pinfunction "PA01_2") (pintype "bidirectional"))
      (node (ref "X1") (pin "1") (pinfunction "1_1") (pintype "passive"))
    )
    (net (code "85") (name "Net-(U3-PA02)") (class "Default")
      (node (ref "U3") (pin "3") (pinfunction "PA02_3") (pintype "bidirectional"))
      (node (ref "U4") (pin "10") (pinfunction "O_10") (pintype "output"))
    )
    (net (code "86") (name "Net-(U3-PA03)") (class "Default")
      (node (ref "U3") (pin "4") (pinfunction "PA03_4") (pintype "bidirectional"))
      (node (ref "U4") (pin "12") (pinfunction "O_12") (pintype "output"))
    )
    (net (code "87") (name "Net-(U3-PA04)") (class "Default")
      (node (ref "R1") (pin "1") (pinfunction "1_1") (pintype "passive"))
      (node (ref "R2") (pin "2") (pinfunction "2_2") (pintype "passive"))
      (node (ref "U3") (pin "13") (pinfunction "PA04_13") (pintype "bidirectional"))
    )
    (net (code "88") (name "Net-(U3-PA05)") (class "Default")
      (node (ref "J10") (pin "3") (pinfunction "3_3") (pintype "passive"))
      (node (ref "U3") (pin "14") (pinfunction "PA05_14") (pintype "bidirectional"))
    )
    (net (code "89") (name "Net-(U3-PA06)") (class "Default")
      (node (ref "J10") (pin "2") (pinfunction "2_2") (pintype "passive"))
      (node (ref "U3") (pin "15") (pinfunction "PA06_15") (pintype "bidirectional"))
    )
    (net (code "90") (name "Net-(U3-PA08)") (class "Default")
      (node (ref "U3") (pin "17") (pinfunction "PA08_17") (pintype "bidirectional"))
      (node (ref "U3") (pin "29") (pinfunction "PA12_29") (pintype "bidirectional"))
    )
    (net (code "91") (name "Net-(U3-PA09)") (class "Default")
      (node (ref "J12") (pin "6") (pinfunction "6_6") (pintype "passive"))
      (node (ref "U3") (pin "18") (pinfunction "PA09_18") (pintype "bidirectional"))
    )
    (net (code "92") (name "Net-(U3-PA10)") (class "Default")
      (node (ref "J12") (pin "3") (pinfunction "3_3") (pintype "passive"))
      (node (ref "U3") (pin "19") (pinfunction "PA10_19") (pintype "bidirectional"))
    )
    (net (code "93") (name "Net-(U3-PA11)") (class "Default")
      (node (ref "J12") (pin "4") (pinfunction "4_4") (pintype "passive"))
      (node (ref "U3") (pin "20") (pinfunction "PA11_20") (pintype "bidirectional"))
    )
    (net (code "94") (name "Net-(U3-PA15)") (class "Default")
      (node (ref "J12") (pin "2") (pinfunction "2_2") (pintype "passive"))
      (node (ref "U3") (pin "32") (pinfunction "PA15_32") (pintype "bidirectional"))
    )
    (net (code "95") (name "Net-(U3-PA24)") (class "Default")
      (node (ref "J11") (pin "2") (pinfunction "2_2") (pintype "passive"))
      (node (ref "U3") (pin "45") (pinfunction "PA24_45") (pintype "bidirectional"))
    )
    (net (code "96") (name "Net-(U3-PA25)") (class "Default")
      (node (ref "J11") (pin "3") (pinfunction "3_3") (pintype "passive"))
      (node (ref "U3") (pin "46") (pinfunction "PA25_46") (pintype "bidirectional"))
    )
    (net (code "97") (name "Net-(U3-PA30)") (class "Default")
      (node (ref "J13") (pin "4") (pinfunction "4_4") (pintype "passive"))
      (node (ref "R4") (pin "1") (pinfunction "1_1") (pintype "passive"))
      (node (ref "U3") (pin "57") (pinfunction "PA30_57") (pintype "bidirectional"))
    )
    (net (code "98") (name "Net-(U3-PA31)") (class "Default")
      (node (ref "J13") (pin "2") (pinfunction "2_2") (pintype "passive"))
      (node (ref "U3") (pin "58") (pinfunction "PA31_58") (pintype "bidirectional"))
    )
    (net (code "99") (name "Net-(U3-PB17)") (class "Default")
      (node (ref "J12") (pin "8") (pinfunction "8_8") (pintype "passive"))
      (node (ref "U3") (pin "40") (pinfunction "PB17_40") (pintype "bidirectional"))
    )
    (net (code "100") (name "Net-(U3-VDDCORE)") (class "Default")
      (node (ref "C15") (pin "1") (pinfunction "1_1") (pintype "passive"))
      (node (ref "U3") (pin "55") (pinfunction "VDDCORE_55") (pintype "bidirectional"))
    )
    (net (code "101") (name "Net-(U3-~{RESET})") (class "Default")
      (node (ref "J13") (pin "10") (pinfunction "10_10") (pintype "passive"))
      (node (ref "U3") (pin "52") (pinfunction "~{RESET}_52") (pintype "input"))
    )
    (net (code "102") (name "Net-(U4E-I)") (class "Default")
      (node (ref "J6") (pin "7") (pinfunction "7_7") (pintype "passive"))
      (node (ref "U4") (pin "11") (pinfunction "I_11") (pintype "input"))
    )
    (net (code "103") (name "Net-(U4F-I)") (class "Default")
      (node (ref "J6") (pin "5") (pinfunction "5_5") (pintype "passive"))
      (node (ref "U4") (pin "13") (pinfunction "I_13") (pintype "input"))
    )
    (net (code "104") (name "unconnected-(J1-D+-Pad3)") (class "Default")
      (node (ref "J1") (pin "3") (pinfunction "D+_3") (pintype "bidirectional"))
    )
    (net (code "105") (name "unconnected-(J1-D--Pad2)") (class "Default")
      (node (ref "J1") (pin "2") (pinfunction "D-_2") (pintype "bidirectional"))
    )
    (net (code "106") (name "unconnected-(J1-ID-Pad4)") (class "Default")
      (node (ref "J1") (pin "4") (pinfunction "ID_4") (pintype "passive"))
    )
    (net (code "107") (name "unconnected-(J6-Pad11)") (class "Default")
      (node (ref "J6") (pin "11") (pinfunction "11_11") (pintype "passive"))
    )
    (net (code "108") (name "unconnected-(J7-Pad11)") (class "Default")
      (node (ref "J7") (pin "11") (pinfunction "11_11") (pintype "passive"))
    )
    (net (code "109") (name "unconnected-(J8-Pad11)") (class "Default")
      (node (ref "J8") (pin "11") (pinfunction "11_11") (pintype "passive"))
    )
    (net (code "110") (name "unconnected-(J9-Pad11)") (class "Default")
      (node (ref "J9") (pin "11") (pinfunction "11_11") (pintype "passive"))
    )
    (net (code "111") (name "unconnected-(J12-Pad1)") (class "Default")
      (node (ref "J12") (pin "1") (pinfunction "1_1") (pintype "passive"))
    )
    (net (code "112") (name "unconnected-(J12-Pad7)") (class "Default")
      (node (ref "J12") (pin "7") (pinfunction "7_7") (pintype "passive"))
    )
    (net (code "113") (name "unconnected-(J13-Pad6)") (class "Default")
      (node (ref "J13") (pin "6") (pinfunction "6_6") (pintype "passive"))
    )
    (net (code "114") (name "unconnected-(J13-Pad7)") (class "Default")
      (node (ref "J13") (pin "7") (pinfunction "7_7") (pintype "passive"))
    )
    (net (code "115") (name "unconnected-(J13-Pad8)") (class "Default")
      (node (ref "J13") (pin "8") (pinfunction "8_8") (pintype "passive"))
    )
    (net (code "116") (name "unconnected-(J13-Pad9)") (class "Default")
      (node (ref "J13") (pin "9") (pinfunction "9_9") (pintype "passive"))
    )
    (net (code "117") (name "unconnected-(J14-P11-Pad11)") (class "Default")
      (node (ref "J14") (pin "11") (pinfunction "P11_11") (pintype "passive"))
    )
    (net (code "118") (name "unconnected-(J14-P12-Pad12)") (class "Default")
      (node (ref "J14") (pin "12") (pinfunction "P12_12") (pintype "passive"))
    )
    (net (code "119") (name "unconnected-(SW1-NO-Pad3)") (class "Default")
      (node (ref "SW1") (pin "3") (pinfunction "NO_3") (pintype "passive"))
    )
    (net (code "120") (name "unconnected-(U4A-O-Pad2)") (class "Default")
      (node (ref "U4") (pin "2") (pinfunction "O_2") (pintype "output"))
    )
    (net (code "121") (name "unconnected-(U4B-O-Pad4)") (class "Default")
      (node (ref "U4") (pin "4") (pinfunction "O_4") (pintype "output"))
    )
    (net (code "122") (name "unconnected-(U4C-O-Pad6)") (class "Default")
      (node (ref "U4") (pin "6") (pinfunction "O_6") (pintype "output"))
    )
    (net (code "123") (name "unconnected-(U4D-O-Pad8)") (class "Default")
      (node (ref "U4") (pin "8") (pinfunction "O_8") (pintype "output"))
    )
  )
)
